# DM_V1_JTAG_CONF_connectors.net
KiCad netlist of a schematic drawn in Altium Designer
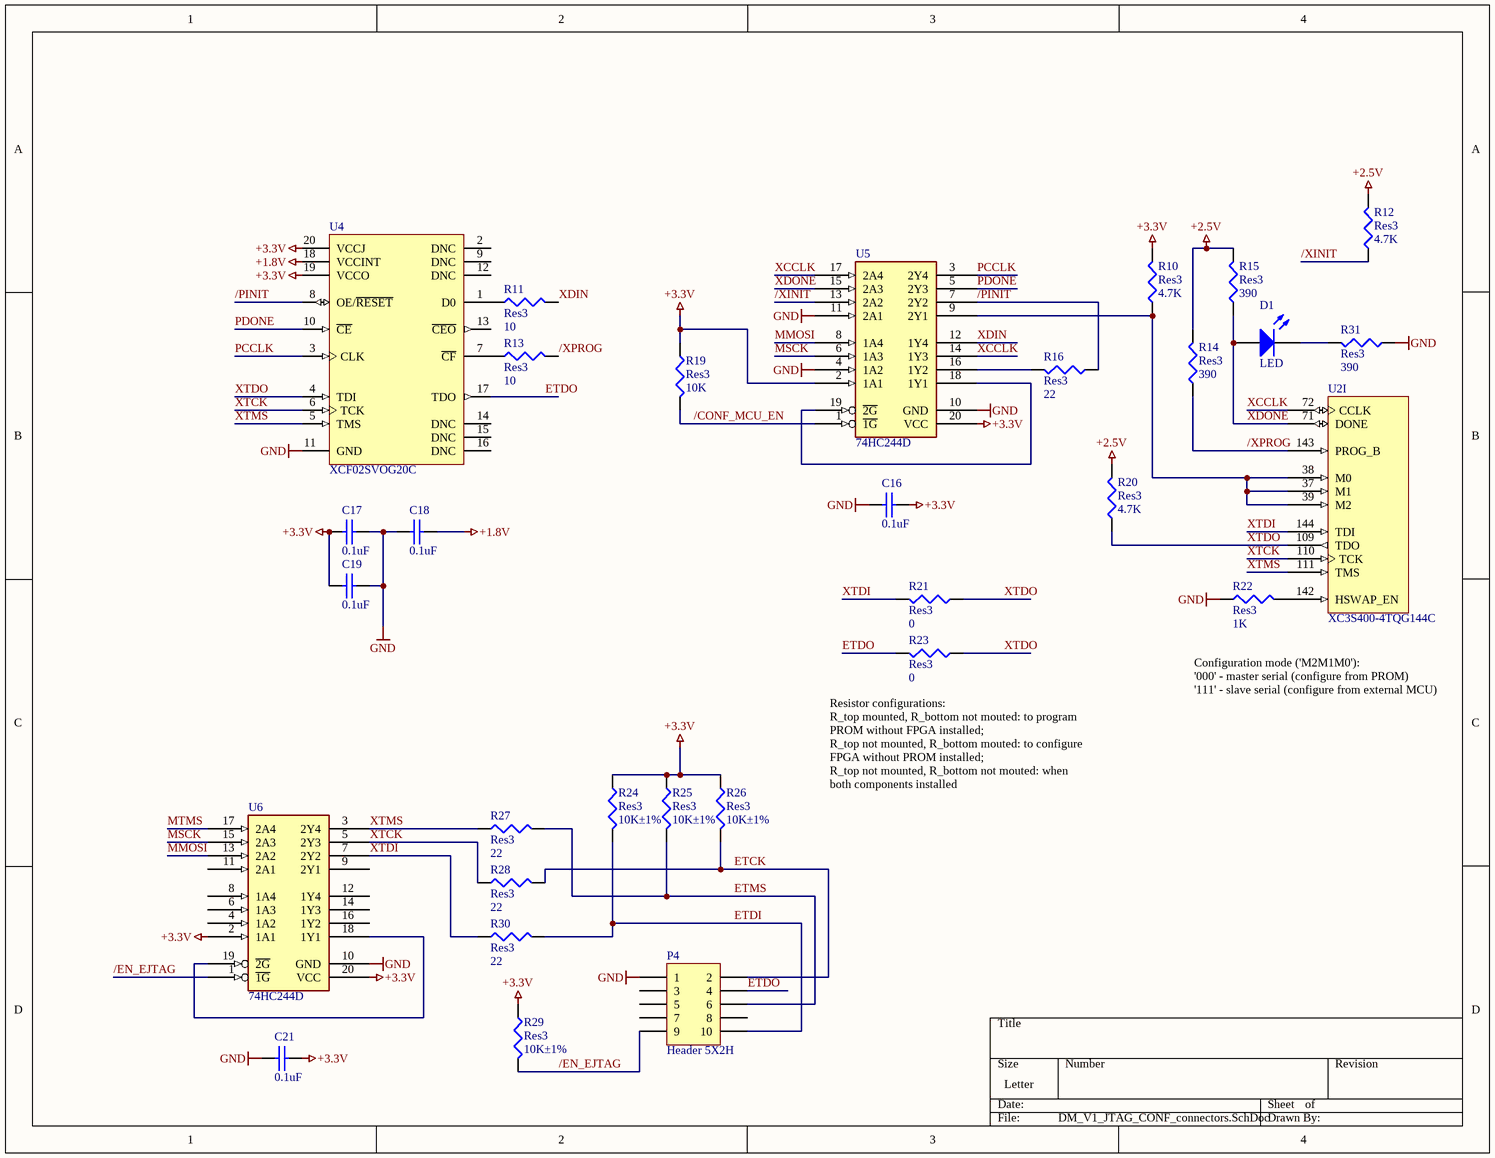
[diagram p0: DM_V1_JTAG_CONF_connectors.SchDoc]

(export (version "E")
  (design (tool "Eeschema 10.0.6"))
  (components
    (comp (ref "C16")
      (value "0.1uF")
      (footprint "1608[0603]")
      (description "Ceramic Chip-capacitor 0603")
      (fields (field (name "VOLTAGE") "25") (field (name "Comment") "0.1"))
      (libsource (lib "ISCapacitor") (part "CC0603-0.1MKF X7R"))
    )
    (comp (ref "C17")
      (value "0.1uF")
      (footprint "1608[0603]")
      (description "Ceramic Chip-capacitor 0603")
      (fields (field (name "VOLTAGE") "25") (field (name "Comment") "0.1"))
      (libsource (lib "ISCapacitor") (part "CC0603-0.1MKF X7R"))
    )
    (comp (ref "C18")
      (value "0.1uF")
      (footprint "1608[0603]")
      (description "Ceramic Chip-capacitor 0603")
      (fields (field (name "VOLTAGE") "25") (field (name "Comment") "0.1"))
      (libsource (lib "ISCapacitor") (part "CC0603-0.1MKF X7R"))
    )
    (comp (ref "C19")
      (value "0.1uF")
      (footprint "1608[0603]")
      (description "Ceramic Chip-capacitor 0603")
      (fields (field (name "VOLTAGE") "25") (field (name "Comment") "0.1"))
      (libsource (lib "ISCapacitor") (part "CC0603-0.1MKF X7R"))
    )
    (comp (ref "C21")
      (value "0.1uF")
      (footprint "1608[0603]")
      (description "Ceramic Chip-capacitor 0603")
      (fields (field (name "VOLTAGE") "25") (field (name "Comment") "0.1"))
      (libsource (lib "ISCapacitor") (part "CC0603-0.1MKF X7R"))
    )
    (comp (ref "D1")
      (value "LED")
      (footprint "1608[0603]")
      (description "Typical RED, GREEN, YELLOW, AMBER GaAs LED")
      (fields (field (name "PUBLISHER") "Altium Limited"))
      (libsource (lib "Miscellaneous Devices") (part "LED2"))
    )
    (comp (ref "P4")
      (value "Header 5X2H")
      (footprint "HDR2X5H")
      (description "Header, 5-Pin, Dual row, Right Angle")
      (fields (field (name "PUBLISHER") "Altium Limited"))
      (libsource (lib "Miscellaneous Connectors") (part "Header 5X2H"))
    )
    (comp (ref "R10")
      (value "Res3")
      (footprint "J1-0603")
      (description "Resistor")
      (fields (field (name "ALTIUM_VALUE") "4.7K") (field (name "PUBLISHER") "Altium Limited"))
      (libsource (lib "Miscellaneous Devices") (part "Res3"))
    )
    (comp (ref "R11")
      (value "Res3")
      (footprint "J1-0603")
      (description "Resistor")
      (fields (field (name "ALTIUM_VALUE") "10") (field (name "PUBLISHER") "Altium Limited"))
      (libsource (lib "Miscellaneous Devices") (part "Res3"))
    )
    (comp (ref "R12")
      (value "Res3")
      (footprint "J1-0603")
      (description "Resistor")
      (fields (field (name "ALTIUM_VALUE") "4.7K") (field (name "PUBLISHER") "Altium Limited"))
      (libsource (lib "Miscellaneous Devices") (part "Res3"))
    )
    (comp (ref "R13")
      (value "Res3")
      (footprint "J1-0603")
      (description "Resistor")
      (fields (field (name "ALTIUM_VALUE") "10") (field (name "PUBLISHER") "Altium Limited"))
      (libsource (lib "Miscellaneous Devices") (part "Res3"))
    )
    (comp (ref "R14")
      (value "Res3")
      (footprint "J1-0603")
      (description "Resistor")
      (fields (field (name "ALTIUM_VALUE") "390") (field (name "PUBLISHER") "Altium Limited"))
      (libsource (lib "Miscellaneous Devices") (part "Res3"))
    )
    (comp (ref "R15")
      (value "Res3")
      (footprint "J1-0603")
      (description "Resistor")
      (fields (field (name "ALTIUM_VALUE") "390") (field (name "PUBLISHER") "Altium Limited"))
      (libsource (lib "Miscellaneous Devices") (part "Res3"))
    )
    (comp (ref "R16")
      (value "Res3")
      (footprint "J1-0603")
      (description "Resistor")
      (fields (field (name "ALTIUM_VALUE") "22") (field (name "PUBLISHER") "Altium Limited"))
      (libsource (lib "Miscellaneous Devices") (part "Res3"))
    )
    (comp (ref "R19")
      (value "Res3")
      (footprint "J1-0603")
      (description "Resistor")
      (fields (field (name "ALTIUM_VALUE") "10K") (field (name "PUBLISHER") "Altium Limited"))
      (libsource (lib "Miscellaneous Devices") (part "Res3"))
    )
    (comp (ref "R20")
      (value "Res3")
      (footprint "J1-0603")
      (description "Resistor")
      (fields (field (name "ALTIUM_VALUE") "4.7K") (field (name "PUBLISHER") "Altium Limited"))
      (libsource (lib "Miscellaneous Devices") (part "Res3"))
    )
    (comp (ref "R21")
      (value "Res3")
      (footprint "J1-0603")
      (description "Resistor")
      (fields (field (name "ALTIUM_VALUE") "0") (field (name "PUBLISHER") "Altium Limited"))
      (libsource (lib "Miscellaneous Devices") (part "Res3"))
    )
    (comp (ref "R22")
      (value "Res3")
      (footprint "J1-0603")
      (description "Resistor")
      (fields (field (name "ALTIUM_VALUE") "1K") (field (name "PUBLISHER") "Altium Limited"))
      (libsource (lib "Miscellaneous Devices") (part "Res3"))
    )
    (comp (ref "R23")
      (value "Res3")
      (footprint "J1-0603")
      (description "Resistor")
      (fields (field (name "ALTIUM_VALUE") "0") (field (name "PUBLISHER") "Altium Limited"))
      (libsource (lib "Miscellaneous Devices") (part "Res3"))
    )
    (comp (ref "R24")
      (value "Res3")
      (footprint "J1-0603")
      (description "Resistor")
      (fields (field (name "ALTIUM_VALUE") "10K±1%") (field (name "PUBLISHER") "Altium Limited"))
      (libsource (lib "Miscellaneous Devices") (part "Res3"))
    )
    (comp (ref "R25")
      (value "Res3")
      (footprint "J1-0603")
      (description "Resistor")
      (fields (field (name "ALTIUM_VALUE") "10K±1%") (field (name "PUBLISHER") "Altium Limited"))
      (libsource (lib "Miscellaneous Devices") (part "Res3"))
    )
    (comp (ref "R26")
      (value "Res3")
      (footprint "J1-0603")
      (description "Resistor")
      (fields (field (name "ALTIUM_VALUE") "10K±1%") (field (name "PUBLISHER") "Altium Limited"))
      (libsource (lib "Miscellaneous Devices") (part "Res3"))
    )
    (comp (ref "R27")
      (value "Res3")
      (footprint "J1-0603")
      (description "Resistor")
      (fields (field (name "ALTIUM_VALUE") "22") (field (name "PUBLISHER") "Altium Limited"))
      (libsource (lib "Miscellaneous Devices") (part "Res3"))
    )
    (comp (ref "R28")
      (value "Res3")
      (footprint "J1-0603")
      (description "Resistor")
      (fields (field (name "ALTIUM_VALUE") "22") (field (name "PUBLISHER") "Altium Limited"))
      (libsource (lib "Miscellaneous Devices") (part "Res3"))
    )
    (comp (ref "R29")
      (value "Res3")
      (footprint "J1-0603")
      (description "Resistor")
      (fields (field (name "ALTIUM_VALUE") "10K±1%") (field (name "PUBLISHER") "Altium Limited"))
      (libsource (lib "Miscellaneous Devices") (part "Res3"))
    )
    (comp (ref "R30")
      (value "Res3")
      (footprint "J1-0603")
      (description "Resistor")
      (fields (field (name "ALTIUM_VALUE") "22") (field (name "PUBLISHER") "Altium Limited"))
      (libsource (lib "Miscellaneous Devices") (part "Res3"))
    )
    (comp (ref "R31")
      (value "Res3")
      (footprint "J1-0603")
      (description "Resistor")
      (fields (field (name "ALTIUM_VALUE") "390") (field (name "PUBLISHER") "Altium Limited"))
      (libsource (lib "Miscellaneous Devices") (part "Res3"))
    )
    (comp (ref "U2")
      (value "XC3S400-4TQG144C")
      (footprint "TQG144_N")
      (description "Spartan-3 1.2V FPGA, 97 User I/Os, 144-Pin TQFP, Standard Performance, Commercial Grade, Pb-Free")
      (fields (field (name "PUBLISHER") "Altium Limited"))
      (libsource (lib "Xilinx Spartan-3") (part "XC3S400-4TQG144C"))
    )
    (comp (ref "U4")
      (value "XCF02SVOG20C")
      (footprint "VOG20_N")
      (fields (field (name "PUBLISHER") "Altium Limited"))
      (libsource (lib "Xilinx XCF") (part "XCF02SVOG20C"))
    )
    (comp (ref "U5")
      (value "74HC244D")
      (footprint "SOP127P1030X265-20N")
      (description "Octal Buffer/Driver Noninverting 3-State Output")
      (libsource (lib "ISLogic") (part "74ALVC244PW"))
    )
    (comp (ref "U6")
      (value "74HC244D")
      (footprint "SOP127P1030X265-20N")
      (description "Octal Buffer/Driver Noninverting 3-State Output")
      (libsource (lib "ISLogic") (part "74ALVC244PW"))
    )
  )
  (nets
    (net (code "1") (name "+1.8V") (class "Default")
      (node (ref "C18") (pin "1") (pintype "passive"))
      (node (ref "U4") (pin "18") (pinfunction "VCCINT_18") (pintype "power_in"))
    )
    (net (code "2") (name "+2.5V") (class "Default")
      (node (ref "R12") (pin "2") (pinfunction "2_2") (pintype "passive"))
      (node (ref "R14") (pin "2") (pinfunction "2_2") (pintype "passive"))
      (node (ref "R15") (pin "2") (pinfunction "2_2") (pintype "passive"))
      (node (ref "R20") (pin "2") (pinfunction "2_2") (pintype "passive"))
    )
    (net (code "3") (name "+3.3V") (class "Default")
      (node (ref "C16") (pin "1") (pintype "passive"))
      (node (ref "C17") (pin "2") (pintype "passive"))
      (node (ref "C19") (pin "2") (pintype "passive"))
      (node (ref "C21") (pin "1") (pintype "passive"))
      (node (ref "R10") (pin "2") (pinfunction "2_2") (pintype "passive"))
      (node (ref "R19") (pin "1") (pinfunction "1_1") (pintype "passive"))
      (node (ref "R24") (pin "1") (pinfunction "1_1") (pintype "passive"))
      (node (ref "R25") (pin "1") (pinfunction "1_1") (pintype "passive"))
      (node (ref "R26") (pin "1") (pinfunction "1_1") (pintype "passive"))
      (node (ref "R29") (pin "1") (pinfunction "1_1") (pintype "passive"))
      (node (ref "U4") (pin "19") (pinfunction "VCCO_19") (pintype "power_in"))
      (node (ref "U4") (pin "20") (pinfunction "VCCJ_20") (pintype "power_in"))
      (node (ref "U5") (pin "2") (pinfunction "1A1_2") (pintype "input"))
      (node (ref "U5") (pin "20") (pinfunction "VCC_20") (pintype "power_in"))
      (node (ref "U6") (pin "2") (pinfunction "1A1_2") (pintype "input"))
      (node (ref "U6") (pin "20") (pinfunction "VCC_20") (pintype "power_in"))
    )
    (net (code "4") (name "/ETCK") (class "Default")
      (node (ref "P4") (pin "2") (pinfunction "2_2") (pintype "passive"))
      (node (ref "R26") (pin "2") (pinfunction "2_2") (pintype "passive"))
      (node (ref "R28") (pin "2") (pinfunction "2_2") (pintype "passive"))
    )
    (net (code "5") (name "/ETDI") (class "Default")
      (node (ref "P4") (pin "10") (pinfunction "10_10") (pintype "passive"))
      (node (ref "R24") (pin "2") (pinfunction "2_2") (pintype "passive"))
      (node (ref "R30") (pin "2") (pinfunction "2_2") (pintype "passive"))
    )
    (net (code "6") (name "/ETDO") (class "Default")
      (node (ref "P4") (pin "4") (pinfunction "4_4") (pintype "passive"))
      (node (ref "R23") (pin "2") (pinfunction "2_2") (pintype "passive"))
      (node (ref "U4") (pin "17") (pinfunction "TDO_17") (pintype "output"))
    )
    (net (code "7") (name "/ETMS") (class "Default")
      (node (ref "P4") (pin "6") (pinfunction "6_6") (pintype "passive"))
      (node (ref "R25") (pin "2") (pinfunction "2_2") (pintype "passive"))
      (node (ref "R27") (pin "2") (pinfunction "2_2") (pintype "passive"))
    )
    (net (code "8") (name "/MMOSI") (class "Default")
      (node (ref "U5") (pin "8") (pinfunction "1A4_8") (pintype "input"))
      (node (ref "U6") (pin "13") (pinfunction "2A2_13") (pintype "input"))
    )
    (net (code "9") (name "/MSCK") (class "Default")
      (node (ref "U5") (pin "6") (pinfunction "1A3_6") (pintype "input"))
      (node (ref "U6") (pin "15") (pinfunction "2A3_15") (pintype "input"))
    )
    (net (code "10") (name "/MTMS") (class "Default")
      (node (ref "U6") (pin "17") (pinfunction "2A4_17") (pintype "input"))
    )
    (net (code "11") (name "/PCCLK") (class "Default")
      (node (ref "U4") (pin "3") (pinfunction "CLK_3") (pintype "input"))
      (node (ref "U5") (pin "3") (pinfunction "2Y4_3") (pintype "tri_state"))
    )
    (net (code "12") (name "/PDONE") (class "Default")
      (node (ref "U4") (pin "10") (pinfunction "~{CE}_10") (pintype "input"))
      (node (ref "U5") (pin "5") (pinfunction "2Y3_5") (pintype "tri_state"))
    )
    (net (code "13") (name "/XCCLK") (class "Default")
      (node (ref "U2") (pin "72") (pinfunction "CCLK_72") (pintype "bidirectional"))
      (node (ref "U5") (pin "14") (pinfunction "1Y3_14") (pintype "tri_state"))
      (node (ref "U5") (pin "17") (pinfunction "2A4_17") (pintype "input"))
    )
    (net (code "14") (name "/XDIN") (class "Default")
      (node (ref "R11") (pin "2") (pinfunction "2_2") (pintype "passive"))
      (node (ref "U5") (pin "12") (pinfunction "1Y4_12") (pintype "tri_state"))
    )
    (net (code "15") (name "/XDONE") (class "Default")
      (node (ref "D1") (pin "1") (pinfunction "A_1") (pintype "passive"))
      (node (ref "R15") (pin "1") (pinfunction "1_1") (pintype "passive"))
      (node (ref "U2") (pin "71") (pinfunction "DONE_71") (pintype "bidirectional"))
      (node (ref "U5") (pin "15") (pinfunction "2A3_15") (pintype "input"))
    )
    (net (code "16") (name "/XTCK") (class "Default")
      (node (ref "R28") (pin "1") (pinfunction "1_1") (pintype "passive"))
      (node (ref "U2") (pin "110") (pinfunction "TCK_110") (pintype "input"))
      (node (ref "U4") (pin "6") (pinfunction "TCK_6") (pintype "input"))
      (node (ref "U6") (pin "5") (pinfunction "2Y3_5") (pintype "tri_state"))
    )
    (net (code "17") (name "/XTDI") (class "Default")
      (node (ref "R21") (pin "2") (pinfunction "2_2") (pintype "passive"))
      (node (ref "R30") (pin "1") (pinfunction "1_1") (pintype "passive"))
      (node (ref "U2") (pin "144") (pinfunction "TDI_144") (pintype "input"))
      (node (ref "U6") (pin "7") (pinfunction "2Y2_7") (pintype "tri_state"))
    )
    (net (code "18") (name "/XTDO") (class "Default")
      (node (ref "R20") (pin "1") (pinfunction "1_1") (pintype "passive"))
      (node (ref "R21") (pin "1") (pinfunction "1_1") (pintype "passive"))
      (node (ref "R23") (pin "1") (pinfunction "1_1") (pintype "passive"))
      (node (ref "U2") (pin "109") (pinfunction "TDO_109") (pintype "output"))
      (node (ref "U4") (pin "4") (pinfunction "TDI_4") (pintype "input"))
    )
    (net (code "19") (name "/XTMS") (class "Default")
      (node (ref "R27") (pin "1") (pinfunction "1_1") (pintype "passive"))
      (node (ref "U2") (pin "111") (pinfunction "TMS_111") (pintype "input"))
      (node (ref "U4") (pin "5") (pinfunction "TMS_5") (pintype "input"))
      (node (ref "U6") (pin "3") (pinfunction "2Y4_3") (pintype "tri_state"))
    )
    (net (code "20") (name "/{slash}CONF_MCU_EN") (class "Default")
      (node (ref "R19") (pin "2") (pinfunction "2_2") (pintype "passive"))
      (node (ref "U5") (pin "1") (pinfunction "~{1G}_1") (pintype "input"))
    )
    (net (code "21") (name "/{slash}EN_EJTAG") (class "Default")
      (node (ref "P4") (pin "9") (pinfunction "9_9") (pintype "passive"))
      (node (ref "R29") (pin "2") (pinfunction "2_2") (pintype "passive"))
      (node (ref "U6") (pin "1") (pinfunction "~{1G}_1") (pintype "input"))
    )
    (net (code "22") (name "/{slash}PINIT") (class "Default")
      (node (ref "R16") (pin "1") (pinfunction "1_1") (pintype "passive"))
      (node (ref "U4") (pin "8") (pinfunction "OE/~{RESET}_8") (pintype "bidirectional"))
      (node (ref "U5") (pin "7") (pinfunction "2Y2_7") (pintype "tri_state"))
    )
    (net (code "23") (name "/{slash}XINIT") (class "Default")
      (node (ref "R12") (pin "1") (pinfunction "1_1") (pintype "passive"))
      (node (ref "U5") (pin "13") (pinfunction "2A2_13") (pintype "input"))
    )
    (net (code "24") (name "/{slash}XPROG") (class "Default")
      (node (ref "R13") (pin "2") (pinfunction "2_2") (pintype "passive"))
      (node (ref "R14") (pin "1") (pinfunction "1_1") (pintype "passive"))
      (node (ref "U2") (pin "143") (pinfunction "PROG_B_143") (pintype "input"))
    )
    (net (code "25") (name "GND") (class "Default")
      (node (ref "C16") (pin "2") (pintype "passive"))
      (node (ref "C17") (pin "1") (pintype "passive"))
      (node (ref "C18") (pin "2") (pintype "passive"))
      (node (ref "C19") (pin "1") (pintype "passive"))
      (node (ref "C21") (pin "2") (pintype "passive"))
      (node (ref "P4") (pin "1") (pinfunction "1_1") (pintype "passive"))
      (node (ref "R22") (pin "1") (pinfunction "1_1") (pintype "passive"))
      (node (ref "R31") (pin "1") (pinfunction "1_1") (pintype "passive"))
      (node (ref "U4") (pin "11") (pinfunction "GND_11") (pintype "power_in"))
      (node (ref "U5") (pin "10") (pinfunction "GND_10") (pintype "power_in"))
      (node (ref "U5") (pin "11") (pinfunction "2A1_11") (pintype "input"))
      (node (ref "U5") (pin "4") (pinfunction "1A2_4") (pintype "input"))
      (node (ref "U6") (pin "10") (pinfunction "GND_10") (pintype "power_in"))
    )
    (net (code "26") (name "Net-(D1-K)") (class "Default")
      (node (ref "D1") (pin "2") (pinfunction "K_2") (pintype "passive"))
      (node (ref "R31") (pin "2") (pinfunction "2_2") (pintype "passive"))
    )
    (net (code "27") (name "Net-(U2I-HSWAP_EN)") (class "Default")
      (node (ref "R22") (pin "2") (pinfunction "2_2") (pintype "passive"))
      (node (ref "U2") (pin "142") (pinfunction "HSWAP_EN_142") (pintype "input"))
    )
    (net (code "28") (name "Net-(U2I-M0)") (class "Default")
      (node (ref "R10") (pin "1") (pinfunction "1_1") (pintype "passive"))
      (node (ref "U2") (pin "37") (pinfunction "M1_37") (pintype "input"))
      (node (ref "U2") (pin "38") (pinfunction "M0_38") (pintype "input"))
      (node (ref "U2") (pin "39") (pinfunction "M2_39") (pintype "input"))
      (node (ref "U5") (pin "9") (pinfunction "2Y1_9") (pintype "tri_state"))
    )
    (net (code "29") (name "Net-(U4-D0)") (class "Default")
      (node (ref "R11") (pin "1") (pinfunction "1_1") (pintype "passive"))
      (node (ref "U4") (pin "1") (pinfunction "D0_1") (pintype "tri_state"))
    )
    (net (code "30") (name "Net-(U4-~{CF})") (class "Default")
      (node (ref "R13") (pin "1") (pinfunction "1_1") (pintype "passive"))
      (node (ref "U4") (pin "7") (pinfunction "~{CF}_7") (pintype "open_collector"))
    )
    (net (code "31") (name "Net-(U5-1Y1)") (class "Default")
      (node (ref "U5") (pin "18") (pinfunction "1Y1_18") (pintype "tri_state"))
      (node (ref "U5") (pin "19") (pinfunction "~{2G}_19") (pintype "input"))
    )
    (net (code "32") (name "Net-(U5-1Y2)") (class "Default")
      (node (ref "R16") (pin "2") (pinfunction "2_2") (pintype "passive"))
      (node (ref "U5") (pin "16") (pinfunction "1Y2_16") (pintype "tri_state"))
    )
    (net (code "33") (name "Net-(U6-1Y1)") (class "Default")
      (node (ref "U6") (pin "18") (pinfunction "1Y1_18") (pintype "tri_state"))
      (node (ref "U6") (pin "19") (pinfunction "~{2G}_19") (pintype "input"))
    )
    (net (code "34") (name "unconnected-(P4-Pad3)") (class "Default")
      (node (ref "P4") (pin "3") (pinfunction "3_3") (pintype "passive"))
    )
    (net (code "35") (name "unconnected-(P4-Pad5)") (class "Default")
      (node (ref "P4") (pin "5") (pinfunction "5_5") (pintype "passive"))
    )
    (net (code "36") (name "unconnected-(P4-Pad7)") (class "Default")
      (node (ref "P4") (pin "7") (pinfunction "7_7") (pintype "passive"))
    )
    (net (code "37") (name "unconnected-(P4-Pad8)") (class "Default")
      (node (ref "P4") (pin "8") (pinfunction "8_8") (pintype "passive"))
    )
    (net (code "38") (name "unconnected-(U4-DNC-Pad2)") (class "Default")
      (node (ref "U4") (pin "2") (pinfunction "DNC_2") (pintype "passive"))
    )
    (net (code "39") (name "unconnected-(U4-DNC-Pad9)") (class "Default")
      (node (ref "U4") (pin "9") (pinfunction "DNC_9") (pintype "passive"))
    )
    (net (code "40") (name "unconnected-(U4-DNC-Pad12)") (class "Default")
      (node (ref "U4") (pin "12") (pinfunction "DNC_12") (pintype "passive"))
    )
    (net (code "41") (name "unconnected-(U4-DNC-Pad14)") (class "Default")
      (node (ref "U4") (pin "14") (pinfunction "DNC_14") (pintype "passive"))
    )
    (net (code "42") (name "unconnected-(U4-DNC-Pad15)") (class "Default")
      (node (ref "U4") (pin "15") (pinfunction "DNC_15") (pintype "passive"))
    )
    (net (code "43") (name "unconnected-(U4-DNC-Pad16)") (class "Default")
      (node (ref "U4") (pin "16") (pinfunction "DNC_16") (pintype "passive"))
    )
    (net (code "44") (name "unconnected-(U4-~{CEO}-Pad13)") (class "Default")
      (node (ref "U4") (pin "13") (pinfunction "~{CEO}_13") (pintype "output"))
    )
    (net (code "45") (name "unconnected-(U6-1A2-Pad4)") (class "Default")
      (node (ref "U6") (pin "4") (pinfunction "1A2_4") (pintype "input"))
    )
    (net (code "46") (name "unconnected-(U6-1A3-Pad6)") (class "Default")
      (node (ref "U6") (pin "6") (pinfunction "1A3_6") (pintype "input"))
    )
    (net (code "47") (name "unconnected-(U6-1A4-Pad8)") (class "Default")
      (node (ref "U6") (pin "8") (pinfunction "1A4_8") (pintype "input"))
    )
    (net (code "48") (name "unconnected-(U6-1Y2-Pad16)") (class "Default")
      (node (ref "U6") (pin "16") (pinfunction "1Y2_16") (pintype "tri_state"))
    )
    (net (code "49") (name "unconnected-(U6-1Y3-Pad14)") (class "Default")
      (node (ref "U6") (pin "14") (pinfunction "1Y3_14") (pintype "tri_state"))
    )
    (net (code "50") (name "unconnected-(U6-1Y4-Pad12)") (class "Default")
      (node (ref "U6") (pin "12") (pinfunction "1Y4_12") (pintype "tri_state"))
    )
    (net (code "51") (name "unconnected-(U6-2A1-Pad11)") (class "Default")
      (node (ref "U6") (pin "11") (pinfunction "2A1_11") (pintype "input"))
    )
    (net (code "52") (name "unconnected-(U6-2Y1-Pad9)") (class "Default")
      (node (ref "U6") (pin "9") (pinfunction "2Y1_9") (pintype "tri_state"))
    )
  )
)
